# hnb-switches.net
KiCad netlist of a schematic drawn in EAGLE
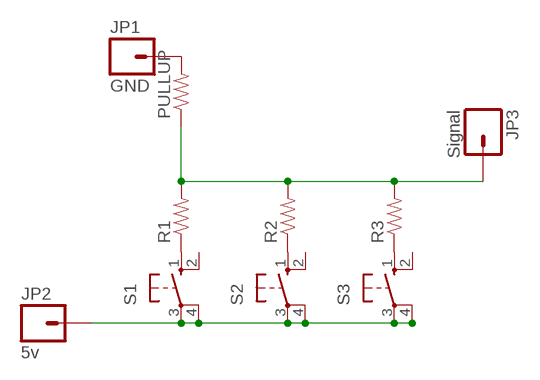
[diagram p0: schematic, sheet 1]

(export (version "E")
  (design (tool "Eeschema 10.0.6"))
  (components
    (comp (ref "JP1")
      (value "GND")
      (footprint "eagle-import:1X01_LONGPAD")
      (libsource (lib "eagle-import") (part "M01PTH_LONGPAD"))
    )
    (comp (ref "JP2")
      (value "5v")
      (footprint "eagle-import:1X01_LONGPAD")
      (libsource (lib "eagle-import") (part "M01PTH_LONGPAD"))
    )
    (comp (ref "JP3")
      (value "Signal")
      (footprint "eagle-import:1X01_LONGPAD")
      (libsource (lib "eagle-import") (part "M01PTH_LONGPAD"))
    )
    (comp (ref "PULLUP")
      (value "RESISTOR1206")
      (footprint "eagle-import:1206")
      (libsource (lib "eagle-import") (part "RESISTOR1206"))
    )
    (comp (ref "R1")
      (value "RESISTOR1206")
      (footprint "eagle-import:1206")
      (libsource (lib "eagle-import") (part "RESISTOR1206"))
    )
    (comp (ref "R2")
      (value "RESISTOR1206")
      (footprint "eagle-import:1206")
      (libsource (lib "eagle-import") (part "RESISTOR1206"))
    )
    (comp (ref "R3")
      (value "RESISTOR1206")
      (footprint "eagle-import:1206")
      (libsource (lib "eagle-import") (part "RESISTOR1206"))
    )
    (comp (ref "S1")
      (value "10-XX")
      (footprint "eagle-import:B3F-10XX")
      (fields (field (name "MPN") "B3F-1000"))
      (libsource (lib "eagle-import") (part "10-XX"))
    )
    (comp (ref "S2")
      (value "10-XX")
      (footprint "eagle-import:B3F-10XX")
      (fields (field (name "MPN") "B3F-1000"))
      (libsource (lib "eagle-import") (part "10-XX"))
    )
    (comp (ref "S3")
      (value "10-XX")
      (footprint "eagle-import:B3F-10XX")
      (fields (field (name "MPN") "B3F-1000"))
      (libsource (lib "eagle-import") (part "10-XX"))
    )
  )
  (nets
    (net (code "1") (name "Net-(JP1-Pad1)") (class "Default")
      (node (ref "JP1") (pin "1") (pinfunction "1_1") (pintype "passive"))
      (node (ref "PULLUP") (pin "2") (pinfunction "2_2") (pintype "passive"))
    )
    (net (code "2") (name "Net-(JP3-Pad1)") (class "Default")
      (node (ref "JP3") (pin "1") (pinfunction "1_1") (pintype "passive"))
      (node (ref "PULLUP") (pin "1") (pinfunction "1_1") (pintype "passive"))
      (node (ref "R1") (pin "2") (pinfunction "2_2") (pintype "passive"))
      (node (ref "R2") (pin "2") (pinfunction "2_2") (pintype "passive"))
      (node (ref "R3") (pin "2") (pinfunction "2_2") (pintype "passive"))
    )
    (net (code "3") (name "Net-(S1-P)") (class "Default")
      (node (ref "JP2") (pin "1") (pinfunction "1_1") (pintype "passive"))
      (node (ref "S1") (pin "3") (pinfunction "P_3") (pintype "passive"))
      (node (ref "S1") (pin "4") (pinfunction "P1_4") (pintype "passive"))
      (node (ref "S2") (pin "3") (pinfunction "P_3") (pintype "passive"))
      (node (ref "S2") (pin "4") (pinfunction "P1_4") (pintype "passive"))
      (node (ref "S3") (pin "3") (pinfunction "P_3") (pintype "passive"))
      (node (ref "S3") (pin "4") (pinfunction "P1_4") (pintype "passive"))
    )
    (net (code "4") (name "Net-(S1-S)") (class "Default")
      (node (ref "R1") (pin "1") (pinfunction "1_1") (pintype "passive"))
      (node (ref "S1") (pin "1") (pinfunction "S_1") (pintype "passive"))
    )
    (net (code "5") (name "Net-(S2-S)") (class "Default")
      (node (ref "R2") (pin "1") (pinfunction "1_1") (pintype "passive"))
      (node (ref "S2") (pin "1") (pinfunction "S_1") (pintype "passive"))
    )
    (net (code "6") (name "Net-(S3-S)") (class "Default")
      (node (ref "R3") (pin "1") (pinfunction "1_1") (pintype "passive"))
      (node (ref "S3") (pin "1") (pinfunction "S_1") (pintype "passive"))
    )
    (net (code "7") (name "unconnected-(S1-S1-Pad2)") (class "Default")
      (node (ref "S1") (pin "2") (pinfunction "S1_2") (pintype "passive"))
    )
    (net (code "8") (name "unconnected-(S2-S1-Pad2)") (class "Default")
      (node (ref "S2") (pin "2") (pinfunction "S1_2") (pintype "passive"))
    )
    (net (code "9") (name "unconnected-(S3-S1-Pad2)") (class "Default")
      (node (ref "S3") (pin "2") (pinfunction "S1_2") (pintype "passive"))
    )
  )
)
